# Sheet2_Charging.net
KiCad netlist of a schematic drawn in Altium Designer
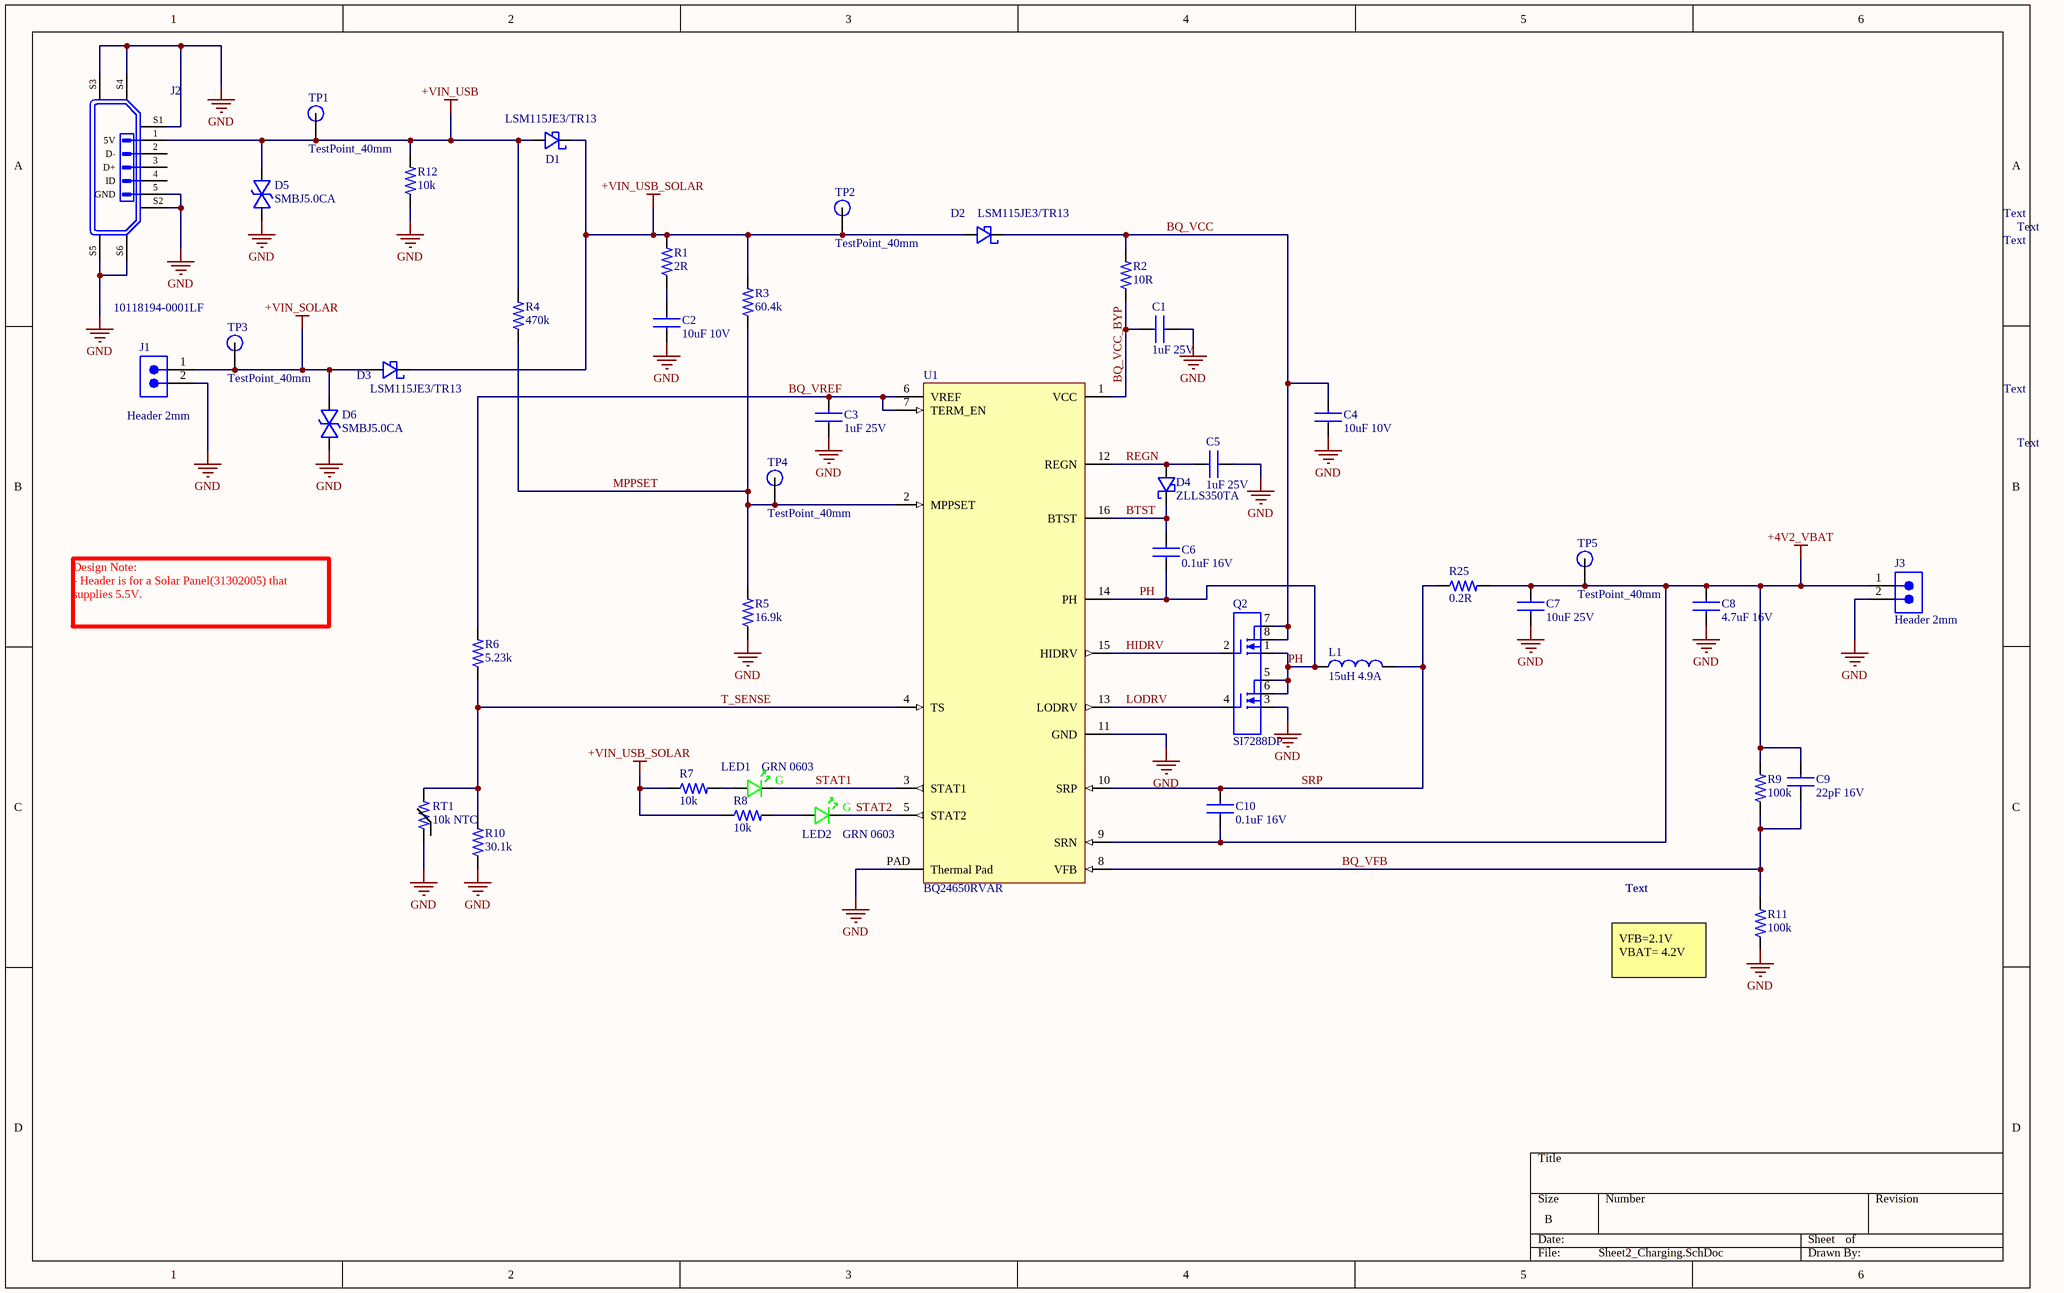
[diagram p0: Sheet2_Charging.SchDoc]

(export (version "E")
  (design (tool "Eeschema 10.0.6"))
  (components
    (comp (ref "C1")
      (value "1uF 25V")
      (footprint "CAP_0805_1_4MM")
      (description "Cap Ceramic 1uF 25V X5R 10% SMD 0805 85C Paper T/R")
      (fields
        (field (name "MANUFACTURER") "Samsung")
        (field (name "MANUFACTURER PART NUMBER") "CL21A105KACLNNC")
      )
      (libsource (lib "LPEDT_Parts") (part "CL21A105KACLNNC"))
    )
    (comp (ref "C2")
      (value "10uF 10V")
      (footprint "CAP_0805_1_4MM")
      (description "CAP CER 2.2UF 10V X5R 0805")
      (fields
        (field (name "MANUFACTURER") "Taiyo Yuden")
        (field (name "MANUFACTURER PART NUMBER") "LMK212BJ225MG-T")
      )
      (libsource (lib "LPEDT_Parts") (part "LMK212BJ225MG-T"))
    )
    (comp (ref "C3")
      (value "1uF 25V")
      (footprint "CAP_0805_1_4MM")
      (description "Cap Ceramic 1uF 25V X5R 10% SMD 0805 85C Paper T/R")
      (fields
        (field (name "MANUFACTURER") "Samsung")
        (field (name "MANUFACTURER PART NUMBER") "CL21A105KACLNNC")
      )
      (libsource (lib "LPEDT_Parts") (part "CL21A105KACLNNC"))
    )
    (comp (ref "C4")
      (value "10uF 10V")
      (footprint "CAP_0805_1_4MM")
      (description "CAP CER 2.2UF 10V X5R 0805")
      (fields
        (field (name "MANUFACTURER") "Taiyo Yuden")
        (field (name "MANUFACTURER PART NUMBER") "LMK212BJ225MG-T")
      )
      (libsource (lib "LPEDT_Parts") (part "LMK212BJ225MG-T"))
    )
    (comp (ref "C5")
      (value "1uF 25V")
      (footprint "CAP_0805_1_4MM")
      (description "Cap Ceramic 1uF 25V X5R 10% SMD 0805 85C Paper T/R")
      (fields
        (field (name "MANUFACTURER") "Samsung")
        (field (name "MANUFACTURER PART NUMBER") "CL21A105KACLNNC")
      )
      (libsource (lib "LPEDT_Parts") (part "CL21A105KACLNNC"))
    )
    (comp (ref "C6")
      (value "0.1uF 16V")
      (footprint "CAP_0805_1_4MM")
      (description "CAP CER 0.1UF 16V X7R 0805")
      (fields
        (field (name "MANUFACTURER") "Yageo")
        (field (name "MANUFACTURER PART NUMBER") "CC0805JRX7R7BB104")
      )
      (libsource (lib "LPEDT_Parts") (part "CC0805JRX7R7BB104"))
    )
    (comp (ref "C7")
      (value "10uF 25V")
      (footprint "CAP_0805_1_4MM")
      (description "CAP CER 10UF 25V X5R 0805")
      (fields
        (field (name "MANUFACTURER") "Murata")
        (field (name "MANUFACTURER PART NUMBER") "GRM21BR61E106KA73K")
      )
      (libsource (lib "LPEDT_Parts") (part "GRM21BR61E106KA73K"))
    )
    (comp (ref "C8")
      (value "4.7uF 16V")
      (footprint "CAP_0805_1_4MM")
      (description "CAP CER 4.7UF 16V X5R 0805")
      (fields
        (field (name "MANUFACTURER") "Samsung")
        (field (name "MANUFACTURER PART NUMBER") "CL21A475KOFNNNG")
      )
      (libsource (lib "LPEDT_Parts") (part "CL21A475KOFNNNG"))
    )
    (comp (ref "C9")
      (value "22pF 16V")
      (footprint "CAP_0805_1_4MM")
      (description "CAP CER 22PF 16V C0G/NP0 0805")
      (fields
        (field (name "MANUFACTURER") "Vishay Vitramon")
        (field (name "MANUFACTURER PART NUMBER") "VJ0805A220KXJPW1BC")
      )
      (libsource (lib "LPEDT_Parts") (part "VJ0805A220KXJPW1BC"))
    )
    (comp (ref "C10")
      (value "0.1uF 16V")
      (footprint "CAP_0805_1_4MM")
      (description "CAP CER 0.1UF 16V X7R 0805")
      (fields
        (field (name "MANUFACTURER") "Yageo")
        (field (name "MANUFACTURER PART NUMBER") "CC0805JRX7R7BB104")
      )
      (libsource (lib "LPEDT_Parts") (part "CC0805JRX7R7BB104"))
    )
    (comp (ref "D1")
      (value "LSM115JE3/TR13")
      (footprint "DIODE_4_31X3_62MM")
      (description "DIODE SCHOTTKY 30V 200MA SOD323")
      (fields (field (name "MANUFACTURER") "Microsemi") (field (name "VOLTAGE") "30V"))
      (libsource (lib "LPEDT_Parts") (part "LSM115JE3/TR13"))
    )
    (comp (ref "D2")
      (value "LSM115JE3/TR13")
      (footprint "DIODE_4_31X3_62MM")
      (description "DIODE SCHOTTKY 30V 200MA SOD323")
      (fields (field (name "MANUFACTURER") "Microsemi") (field (name "VOLTAGE") "30V"))
      (libsource (lib "LPEDT_Parts") (part "LSM115JE3/TR13"))
    )
    (comp (ref "D3")
      (value "LSM115JE3/TR13")
      (footprint "DIODE_4_31X3_62MM")
      (description "DIODE SCHOTTKY 30V 200MA SOD323")
      (fields (field (name "MANUFACTURER") "Microsemi") (field (name "VOLTAGE") "30V"))
      (libsource (lib "LPEDT_Parts") (part "LSM115JE3/TR13"))
    )
    (comp (ref "D4")
      (value "ZLLS350TA")
      (footprint "DIODE-SOD_08X16")
      (description "Diode Schottky 40V 0.65A 2Pin SOD523")
      (fields (field (name "MANUFACTURER") "Diodes Zetex"))
      (libsource (lib "LPEDT_Parts") (part "ZLLS350TA"))
    )
    (comp (ref "D5")
      (value "SMBJ5.0CA")
      (footprint "DIOM4436X26N")
      (fields (field (name "MANUFACTURER") "Bourns"))
      (libsource (lib "LPEDT_Parts") (part "SMBJ5.0CA"))
    )
    (comp (ref "D6")
      (value "SMBJ5.0CA")
      (footprint "DIOM4436X26N")
      (fields (field (name "MANUFACTURER") "Bourns"))
      (libsource (lib "LPEDT_Parts") (part "SMBJ5.0CA"))
    )
    (comp (ref "J1")
      (value "Header 2mm")
      (footprint "2-PIN_MALE_HEADER_2MM")
      (description "Connector Header, PH Series, 2 Position, 2.00mm, Through Hole, Press-Fit, Solder, Natural")
      (fields
        (field (name "MANUFACTURER") "JST")
        (field (name "MANUFACTURER PART NUMBER") "B2B-PH-K-S(LF)(SN)")
      )
      (libsource (lib "LPEDT_Parts") (part "B2B-PH-K-S(LF)(SN)"))
    )
    (comp (ref "J2")
      (value "micro-USB")
      (footprint "micro-USB")
      (description "10118194-0001LF micro-USB paste-in-pad")
      (fields
        (field (name "MANUFACTURER") "FCI")
        (field (name "MANUFACTURER PART NUMBER") "10118194-0001LF")
        (field (name ".CREATOR") "Kailey Shara")
        (field (name ".SCHCHECKED") "KS")
        (field (name ".PCBCHECKED") "KS")
      )
      (libsource (lib "LPEDT_Parts") (part "micro-USB"))
    )
    (comp (ref "J3")
      (value "Header 2mm")
      (footprint "2-PIN_MALE_HEADER_2MM")
      (description "Connector Header, PH Series, 2 Position, 2.00mm, Through Hole, Press-Fit, Solder, Natural")
      (fields
        (field (name "MANUFACTURER") "JST")
        (field (name "MANUFACTURER PART NUMBER") "B2B-PH-K-S(LF)(SN)")
      )
      (libsource (lib "LPEDT_Parts") (part "B2B-PH-K-S(LF)(SN)"))
    )
    (comp (ref "L1")
      (value "15uH 4.9A")
      (footprint "IND_818X818")
      (description "Inductor High Current Shielded Wirewound 15uH 20% 100KHz 4.9A 65.3mOhm DCR 3232 T/R")
      (fields
        (field (name "MANUFACTURER") "Vishay Dale")
        (field (name "MANUFACTURER PART NUMBER") "IHLP3232DZER150M11")
      )
      (libsource (lib "LPEDT_Parts") (part "IHLP3232DZER150M11"))
    )
    (comp (ref "LED1")
      (value "GRN 0603")
      (footprint "LED_0603_GRN_WL-SMCW")
      (description "LED, 0603, GREEN, 430MCD, 520NM")
      (fields
        (field (name "MANUFACTURER") "Wurth Electronics")
        (field (name "MANUFACTURER PART NUMBER") "150060GS75000")
      )
      (libsource (lib "LPEDT_Parts") (part "150060GS75000"))
    )
    (comp (ref "LED2")
      (value "GRN 0603")
      (footprint "LED_0603_GRN_WL-SMCW")
      (description "LED, 0603, GREEN, 430MCD, 520NM")
      (fields
        (field (name "MANUFACTURER") "Wurth Electronics")
        (field (name "MANUFACTURER PART NUMBER") "150060GS75000")
      )
      (libsource (lib "LPEDT_Parts") (part "150060GS75000"))
    )
    (comp (ref "Q2")
      (value "SI7288DP")
      (footprint "FET-SO8_POWERPAK_515X615")
      (description "VISHAY - SI7288DP-T1-GE3 - MOSFET, DUAL N-CH, 40V, 20A, POWERPAK SO")
      (fields
        (field (name "MANUFACTURER") "Vishay Siliconix")
        (field (name "MANUFACTURER PART NUMBER") "SI7288DP-T1-GE3")
      )
      (libsource (lib "LPEDT_Parts") (part "SI7288DP-T1-GE3"))
    )
    (comp (ref "R1")
      (value "2R")
      (footprint "RES_1206_310X16")
      (fields
        (field (name "MANUFACTURER") "Bourns")
        (field (name "MANUFACTURER PART NUMBER") "CRM1206-JW-2R2ELF")
        (field (name "TOLERANCE") "5%")
      )
      (libsource (lib "LPEDT_Parts") (part "CRM1206-JW-2R2ELF"))
    )
    (comp (ref "R2")
      (value "10R")
      (footprint "RES_1206_310X16")
      (fields
        (field (name "MANUFACTURER") "Panasonic")
        (field (name "MANUFACTURER PART NUMBER") "ERJ8ENF10R0V")
        (field (name "TOLERANCE") "1%")
      )
      (libsource (lib "LPEDT_Parts") (part "ERJ8ENF10R0V"))
    )
    (comp (ref "R3")
      (value "60.4k")
      (footprint "RES_0603_1608X06")
      (fields
        (field (name "MANUFACTURER") "Vishay")
        (field (name "MANUFACTURER PART NUMBER") "CRCW060360K4FKEA")
        (field (name "TOLERANCE") "1%")
      )
      (libsource (lib "LPEDT_Parts") (part "CRCW060360K4FKEA"))
    )
    (comp (ref "R4")
      (value "470k")
      (footprint "RES_0603_1608X06")
      (fields
        (field (name "MANUFACTURER") "Vishay")
        (field (name "MANUFACTURER PART NUMBER") "CRCW0603470KFKEA")
        (field (name "TOLERANCE") "1%")
      )
      (libsource (lib "LPEDT_Parts") (part "CRCW0603470KFKEA"))
    )
    (comp (ref "R5")
      (value "16.9k")
      (footprint "RES_0603_1608X06")
      (description "RES SMD 16.9K OHM 1% 1/4W 0603")
      (fields
        (field (name "MANUFACTURER") "Vishay Dale")
        (field (name "MANUFACTURER PART NUMBER") "CRCW060316K9FKEAHP")
      )
      (libsource (lib "LPEDT_Parts") (part "CRCW060316K9FKEAHP"))
    )
    (comp (ref "R6")
      (value "5.23k")
      (footprint "RES_0603_1608X06")
      (description "RES SMD 5.23K OHM 1% 1/10W 0603")
      (fields
        (field (name "MANUFACTURER") "Stackpole Electronics")
        (field (name "MANUFACTURER PART NUMBER") "RMCF0603FT5K23")
      )
      (libsource (lib "LPEDT_Parts") (part "RMCF0603FT5K23"))
    )
    (comp (ref "R7")
      (value "10k")
      (footprint "RES_0805_2X1_25MM")
      (description "RES 10K OHM 1% 1/8W 0805")
      (fields
        (field (name "MANUFACTURER") "Stackpole Electronics")
        (field (name "MANUFACTURER PART NUMBER") "RMCF0805FT10K0")
      )
      (libsource (lib "LPEDT_Parts") (part "RMCF0805FT10K0"))
    )
    (comp (ref "R8")
      (value "10k")
      (footprint "RES_0805_2X1_25MM")
      (description "RES 10K OHM 1% 1/8W 0805")
      (fields
        (field (name "MANUFACTURER") "Stackpole Electronics")
        (field (name "MANUFACTURER PART NUMBER") "RMCF0805FT10K0")
      )
      (libsource (lib "LPEDT_Parts") (part "RMCF0805FT10K0"))
    )
    (comp (ref "R9")
      (value "100k")
      (footprint "RES_0603_1608X06")
      (description "RES SMD 100K OHM 1% 1/10W 0603")
      (fields
        (field (name "MANUFACTURER") "Yageo")
        (field (name "MANUFACTURER PART NUMBER") "RC0603FR-07100KL")
      )
      (libsource (lib "LPEDT_Parts") (part "RC0603FR-07100KL"))
    )
    (comp (ref "R10")
      (value "30.1k")
      (footprint "RES_0603_1608X06")
      (description "RES SMD 30.1K OHM 1% 1/10W 0603")
      (fields
        (field (name "MANUFACTURER") "Stackpole Electronics")
        (field (name "MANUFACTURER PART NUMBER") "RMCF0603FT30K1")
      )
      (libsource (lib "LPEDT_Parts") (part "RMCF0603FT30K1"))
    )
    (comp (ref "R11")
      (value "100k")
      (footprint "RES_0603_1608X06")
      (description "RES SMD 100K OHM 1% 1/10W 0603")
      (fields
        (field (name "MANUFACTURER") "Yageo")
        (field (name "MANUFACTURER PART NUMBER") "RC0603FR-07100KL")
      )
      (libsource (lib "LPEDT_Parts") (part "RC0603FR-07100KL"))
    )
    (comp (ref "R12")
      (value "10k")
      (footprint "RES_0805_2X1_25MM")
      (description "RES 10K OHM 1% 1/8W 0805")
      (fields
        (field (name "MANUFACTURER") "Stackpole Electronics")
        (field (name "MANUFACTURER PART NUMBER") "RMCF0805FT10K0")
      )
      (libsource (lib "LPEDT_Parts") (part "RMCF0805FT10K0"))
    )
    (comp (ref "R25")
      (value "0.2R")
      (footprint "RES_0603_1608X06")
      (description "Res Thick Film 0603 0.2 Ohm 5% 1/10W ±300ppm/C Molded SMD SMD Paper T/R")
      (libsource (lib "LPEDT_Parts") (part "73L2R20J"))
    )
    (comp (ref "RT1")
      (value "10k NTC")
      (footprint "NTC-2_THRUHOLE")
      (description "THERM NTC 10KOHM 3435K RADIAL")
      (fields
        (field (name "MANUFACTURER") "Vishay BCcomponents")
        (field (name "MANUFACTURER PART NUMBER") "NTCLE101E3C90173")
      )
      (libsource (lib "LPEDT_Parts") (part "NTCLE101E3C90173"))
    )
    (comp (ref "TP1")
      (value "TestPoint_40mm")
      (footprint "TP_40MM")
      (libsource (lib "LPEDT_Parts") (part "TestPoint_40mm"))
    )
    (comp (ref "TP2")
      (value "TestPoint_40mm")
      (footprint "TP_40MM")
      (libsource (lib "LPEDT_Parts") (part "TestPoint_40mm"))
    )
    (comp (ref "TP3")
      (value "TestPoint_40mm")
      (footprint "TP_40MM")
      (libsource (lib "LPEDT_Parts") (part "TestPoint_40mm"))
    )
    (comp (ref "TP4")
      (value "TestPoint_40mm")
      (footprint "TP_40MM")
      (libsource (lib "LPEDT_Parts") (part "TestPoint_40mm"))
    )
    (comp (ref "TP5")
      (value "TestPoint_40mm")
      (footprint "TP_40MM")
      (libsource (lib "LPEDT_Parts") (part "TestPoint_40mm"))
    )
    (comp (ref "U1")
      (value "BQ24650RVAR")
      (footprint "16-QFN_3_5x3_5")
      (fields (field (name "MANUFACTURER") "Texas Instruments"))
      (libsource (lib "LPEDT_Parts") (part "BQ24650RVAR"))
    )
  )
  (nets
    (net (code "1") (name "+4V2_VBAT") (class "Default")
      (node (ref "C10") (pin "2") (pinfunction "2_2") (pintype "passive"))
      (node (ref "C7") (pin "1") (pinfunction "1_1") (pintype "passive"))
      (node (ref "C8") (pin "1") (pinfunction "1_1") (pintype "passive"))
      (node (ref "C9") (pin "2") (pinfunction "2_2") (pintype "passive"))
      (node (ref "J3") (pin "1") (pinfunction "1_1") (pintype "passive"))
      (node (ref "R25") (pin "2") (pinfunction "2_2") (pintype "passive"))
      (node (ref "R9") (pin "2") (pinfunction "2_2") (pintype "passive"))
      (node (ref "TP5") (pin "1") (pinfunction "1_1") (pintype "passive"))
      (node (ref "U1") (pin "9") (pinfunction "SRN_9") (pintype "input"))
    )
    (net (code "2") (name "+VIN_SOLAR") (class "Default")
      (node (ref "D3") (pin "2") (pinfunction "ANODE_2") (pintype "passive"))
      (node (ref "D6") (pin "1") (pinfunction "1_1") (pintype "passive"))
      (node (ref "J1") (pin "1") (pinfunction "1_1") (pintype "passive"))
      (node (ref "TP3") (pin "1") (pinfunction "1_1") (pintype "passive"))
    )
    (net (code "3") (name "+VIN_USB") (class "Default")
      (node (ref "D1") (pin "2") (pinfunction "ANODE_2") (pintype "passive"))
      (node (ref "D5") (pin "1") (pinfunction "1_1") (pintype "passive"))
      (node (ref "J2") (pin "1") (pinfunction "5V_1") (pintype "power_in"))
      (node (ref "R12") (pin "2") (pinfunction "2_2") (pintype "passive"))
      (node (ref "R4") (pin "2") (pinfunction "2_2") (pintype "passive"))
      (node (ref "TP1") (pin "1") (pinfunction "1_1") (pintype "passive"))
    )
    (net (code "4") (name "+VIN_USB_SOLAR") (class "Default")
      (node (ref "D1") (pin "1") (pinfunction "CATHODE_1") (pintype "passive"))
      (node (ref "D2") (pin "2") (pinfunction "ANODE_2") (pintype "passive"))
      (node (ref "D3") (pin "1") (pinfunction "CATHODE_1") (pintype "passive"))
      (node (ref "R1") (pin "2") (pinfunction "2_2") (pintype "passive"))
      (node (ref "R3") (pin "2") (pinfunction "2_2") (pintype "passive"))
      (node (ref "R7") (pin "1") (pinfunction "1_1") (pintype "passive"))
      (node (ref "R8") (pin "1") (pinfunction "1_1") (pintype "passive"))
      (node (ref "TP2") (pin "1") (pinfunction "1_1") (pintype "passive"))
    )
    (net (code "5") (name "/BQ_VCC") (class "Default")
      (node (ref "C4") (pin "1") (pinfunction "1_1") (pintype "passive"))
      (node (ref "D2") (pin "1") (pinfunction "CATHODE_1") (pintype "passive"))
      (node (ref "Q2") (pin "7") (pinfunction "D1_1_7") (pintype "passive"))
      (node (ref "Q2") (pin "8") (pinfunction "D1_2_8") (pintype "passive"))
      (node (ref "R2") (pin "2") (pinfunction "2_2") (pintype "passive"))
    )
    (net (code "6") (name "/BQ_VCC_BYP") (class "Default")
      (node (ref "C1") (pin "1") (pinfunction "1_1") (pintype "passive"))
      (node (ref "R2") (pin "1") (pinfunction "1_1") (pintype "passive"))
      (node (ref "U1") (pin "1") (pinfunction "VCC_1") (pintype "power_in"))
    )
    (net (code "7") (name "/BQ_VFB") (class "Default")
      (node (ref "C9") (pin "1") (pinfunction "1_1") (pintype "passive"))
      (node (ref "R11") (pin "2") (pinfunction "2_2") (pintype "passive"))
      (node (ref "R9") (pin "1") (pinfunction "1_1") (pintype "passive"))
      (node (ref "U1") (pin "8") (pinfunction "VFB_8") (pintype "input"))
    )
    (net (code "8") (name "/BQ_VREF") (class "Default")
      (node (ref "C3") (pin "1") (pinfunction "1_1") (pintype "passive"))
      (node (ref "R6") (pin "2") (pinfunction "2_2") (pintype "passive"))
      (node (ref "U1") (pin "6") (pinfunction "VREF_6") (pintype "power_in"))
      (node (ref "U1") (pin "7") (pinfunction "TERM_EN_7") (pintype "input"))
    )
    (net (code "9") (name "/BTST") (class "Default")
      (node (ref "C6") (pin "1") (pinfunction "1_1") (pintype "passive"))
      (node (ref "D4") (pin "1") (pinfunction "CATHODE_1") (pintype "passive"))
      (node (ref "U1") (pin "16") (pinfunction "BTST_16") (pintype "power_in"))
    )
    (net (code "10") (name "/HIDRV") (class "Default")
      (node (ref "Q2") (pin "2") (pinfunction "G1_2") (pintype "passive"))
      (node (ref "U1") (pin "15") (pinfunction "HIDRV_15") (pintype "output"))
    )
    (net (code "11") (name "/LODRV") (class "Default")
      (node (ref "Q2") (pin "4") (pinfunction "G2_4") (pintype "passive"))
      (node (ref "U1") (pin "13") (pinfunction "LODRV_13") (pintype "output"))
    )
    (net (code "12") (name "/MPPSET") (class "Default")
      (node (ref "R3") (pin "1") (pinfunction "1_1") (pintype "passive"))
      (node (ref "R4") (pin "1") (pinfunction "1_1") (pintype "passive"))
      (node (ref "R5") (pin "2") (pinfunction "2_2") (pintype "passive"))
      (node (ref "TP4") (pin "1") (pinfunction "1_1") (pintype "passive"))
      (node (ref "U1") (pin "2") (pinfunction "MPPSET_2") (pintype "input"))
    )
    (net (code "13") (name "/PH") (class "Default")
      (node (ref "C6") (pin "2") (pinfunction "2_2") (pintype "passive"))
      (node (ref "L1") (pin "1") (pinfunction "1_1") (pintype "passive"))
      (node (ref "Q2") (pin "1") (pinfunction "S1_1") (pintype "passive"))
      (node (ref "Q2") (pin "5") (pinfunction "D2_1_5") (pintype "passive"))
      (node (ref "Q2") (pin "6") (pinfunction "D2_2_6") (pintype "passive"))
      (node (ref "U1") (pin "14") (pinfunction "PH_14") (pintype "power_in"))
    )
    (net (code "14") (name "/REGN") (class "Default")
      (node (ref "C5") (pin "1") (pinfunction "1_1") (pintype "passive"))
      (node (ref "D4") (pin "2") (pinfunction "ANODE_2") (pintype "passive"))
      (node (ref "U1") (pin "12") (pinfunction "REGN_12") (pintype "power_in"))
    )
    (net (code "15") (name "/SRP") (class "Default")
      (node (ref "C10") (pin "1") (pinfunction "1_1") (pintype "passive"))
      (node (ref "L1") (pin "2") (pinfunction "2_2") (pintype "passive"))
      (node (ref "R25") (pin "1") (pinfunction "1_1") (pintype "passive"))
      (node (ref "U1") (pin "10") (pinfunction "SRP_10") (pintype "input"))
    )
    (net (code "16") (name "/STAT1") (class "Default")
      (node (ref "LED1") (pin "C") (pinfunction "C_C") (pintype "passive"))
      (node (ref "U1") (pin "3") (pinfunction "STAT1_3") (pintype "output"))
    )
    (net (code "17") (name "/STAT2") (class "Default")
      (node (ref "LED2") (pin "C") (pinfunction "C_C") (pintype "passive"))
      (node (ref "U1") (pin "5") (pinfunction "STAT2_5") (pintype "output"))
    )
    (net (code "18") (name "/T_SENSE") (class "Default")
      (node (ref "R10") (pin "2") (pinfunction "2_2") (pintype "passive"))
      (node (ref "R6") (pin "1") (pinfunction "1_1") (pintype "passive"))
      (node (ref "RT1") (pin "2") (pinfunction "2_2") (pintype "passive"))
      (node (ref "U1") (pin "4") (pinfunction "TS_4") (pintype "input"))
    )
    (net (code "19") (name "GND") (class "Default")
      (node (ref "C1") (pin "2") (pinfunction "2_2") (pintype "passive"))
      (node (ref "C2") (pin "2") (pinfunction "2_2") (pintype "passive"))
      (node (ref "C3") (pin "2") (pinfunction "2_2") (pintype "passive"))
      (node (ref "C4") (pin "2") (pinfunction "2_2") (pintype "passive"))
      (node (ref "C5") (pin "2") (pinfunction "2_2") (pintype "passive"))
      (node (ref "C7") (pin "2") (pinfunction "2_2") (pintype "passive"))
      (node (ref "C8") (pin "2") (pinfunction "2_2") (pintype "passive"))
      (node (ref "D5") (pin "2") (pinfunction "2_2") (pintype "passive"))
      (node (ref "D6") (pin "2") (pinfunction "2_2") (pintype "passive"))
      (node (ref "J1") (pin "2") (pinfunction "2_2") (pintype "passive"))
      (node (ref "J2") (pin "5") (pinfunction "GND_5") (pintype "power_in"))
      (node (ref "J2") (pin "S1") (pinfunction "GND_S1") (pintype "power_in"))
      (node (ref "J2") (pin "S2") (pinfunction "GND_S2") (pintype "power_in"))
      (node (ref "J2") (pin "S3") (pinfunction "GND_S3") (pintype "power_in"))
      (node (ref "J2") (pin "S4") (pinfunction "GND_S4") (pintype "power_in"))
      (node (ref "J2") (pin "S5") (pinfunction "GND_S5") (pintype "power_in"))
      (node (ref "J2") (pin "S6") (pinfunction "GND_S6") (pintype "power_in"))
      (node (ref "J3") (pin "2") (pinfunction "2_2") (pintype "passive"))
      (node (ref "Q2") (pin "3") (pinfunction "S2_3") (pintype "passive"))
      (node (ref "R10") (pin "1") (pinfunction "1_1") (pintype "passive"))
      (node (ref "R11") (pin "1") (pinfunction "1_1") (pintype "passive"))
      (node (ref "R12") (pin "1") (pinfunction "1_1") (pintype "passive"))
      (node (ref "R5") (pin "1") (pinfunction "1_1") (pintype "passive"))
      (node (ref "RT1") (pin "1") (pinfunction "1_1") (pintype "passive"))
      (node (ref "U1") (pin "11") (pinfunction "GND_11") (pintype "power_in"))
      (node (ref "U1") (pin "PAD") (pinfunction "Thermal_Pad_PAD") (pintype "power_in"))
    )
    (net (code "20") (name "Net-(C2-Pad1)") (class "Default")
      (node (ref "C2") (pin "1") (pinfunction "1_1") (pintype "passive"))
      (node (ref "R1") (pin "1") (pinfunction "1_1") (pintype "passive"))
    )
    (net (code "21") (name "Net-(LED1-PadA)") (class "Default")
      (node (ref "LED1") (pin "A") (pinfunction "A_A") (pintype "passive"))
      (node (ref "R7") (pin "2") (pinfunction "2_2") (pintype "passive"))
    )
    (net (code "22") (name "Net-(LED2-PadA)") (class "Default")
      (node (ref "LED2") (pin "A") (pinfunction "A_A") (pintype "passive"))
      (node (ref "R8") (pin "2") (pinfunction "2_2") (pintype "passive"))
    )
    (net (code "23") (name "unconnected-(J2-D+-Pad3)") (class "Default")
      (node (ref "J2") (pin "3") (pinfunction "D+_3") (pintype "passive"))
    )
    (net (code "24") (name "unconnected-(J2-D--Pad2)") (class "Default")
      (node (ref "J2") (pin "2") (pinfunction "D-_2") (pintype "passive"))
    )
    (net (code "25") (name "unconnected-(J2-ID-Pad4)") (class "Default")
      (node (ref "J2") (pin "4") (pinfunction "ID_4") (pintype "passive"))
    )
  )
)
